# hack.net
KiCad netlist of a schematic drawn in EAGLE
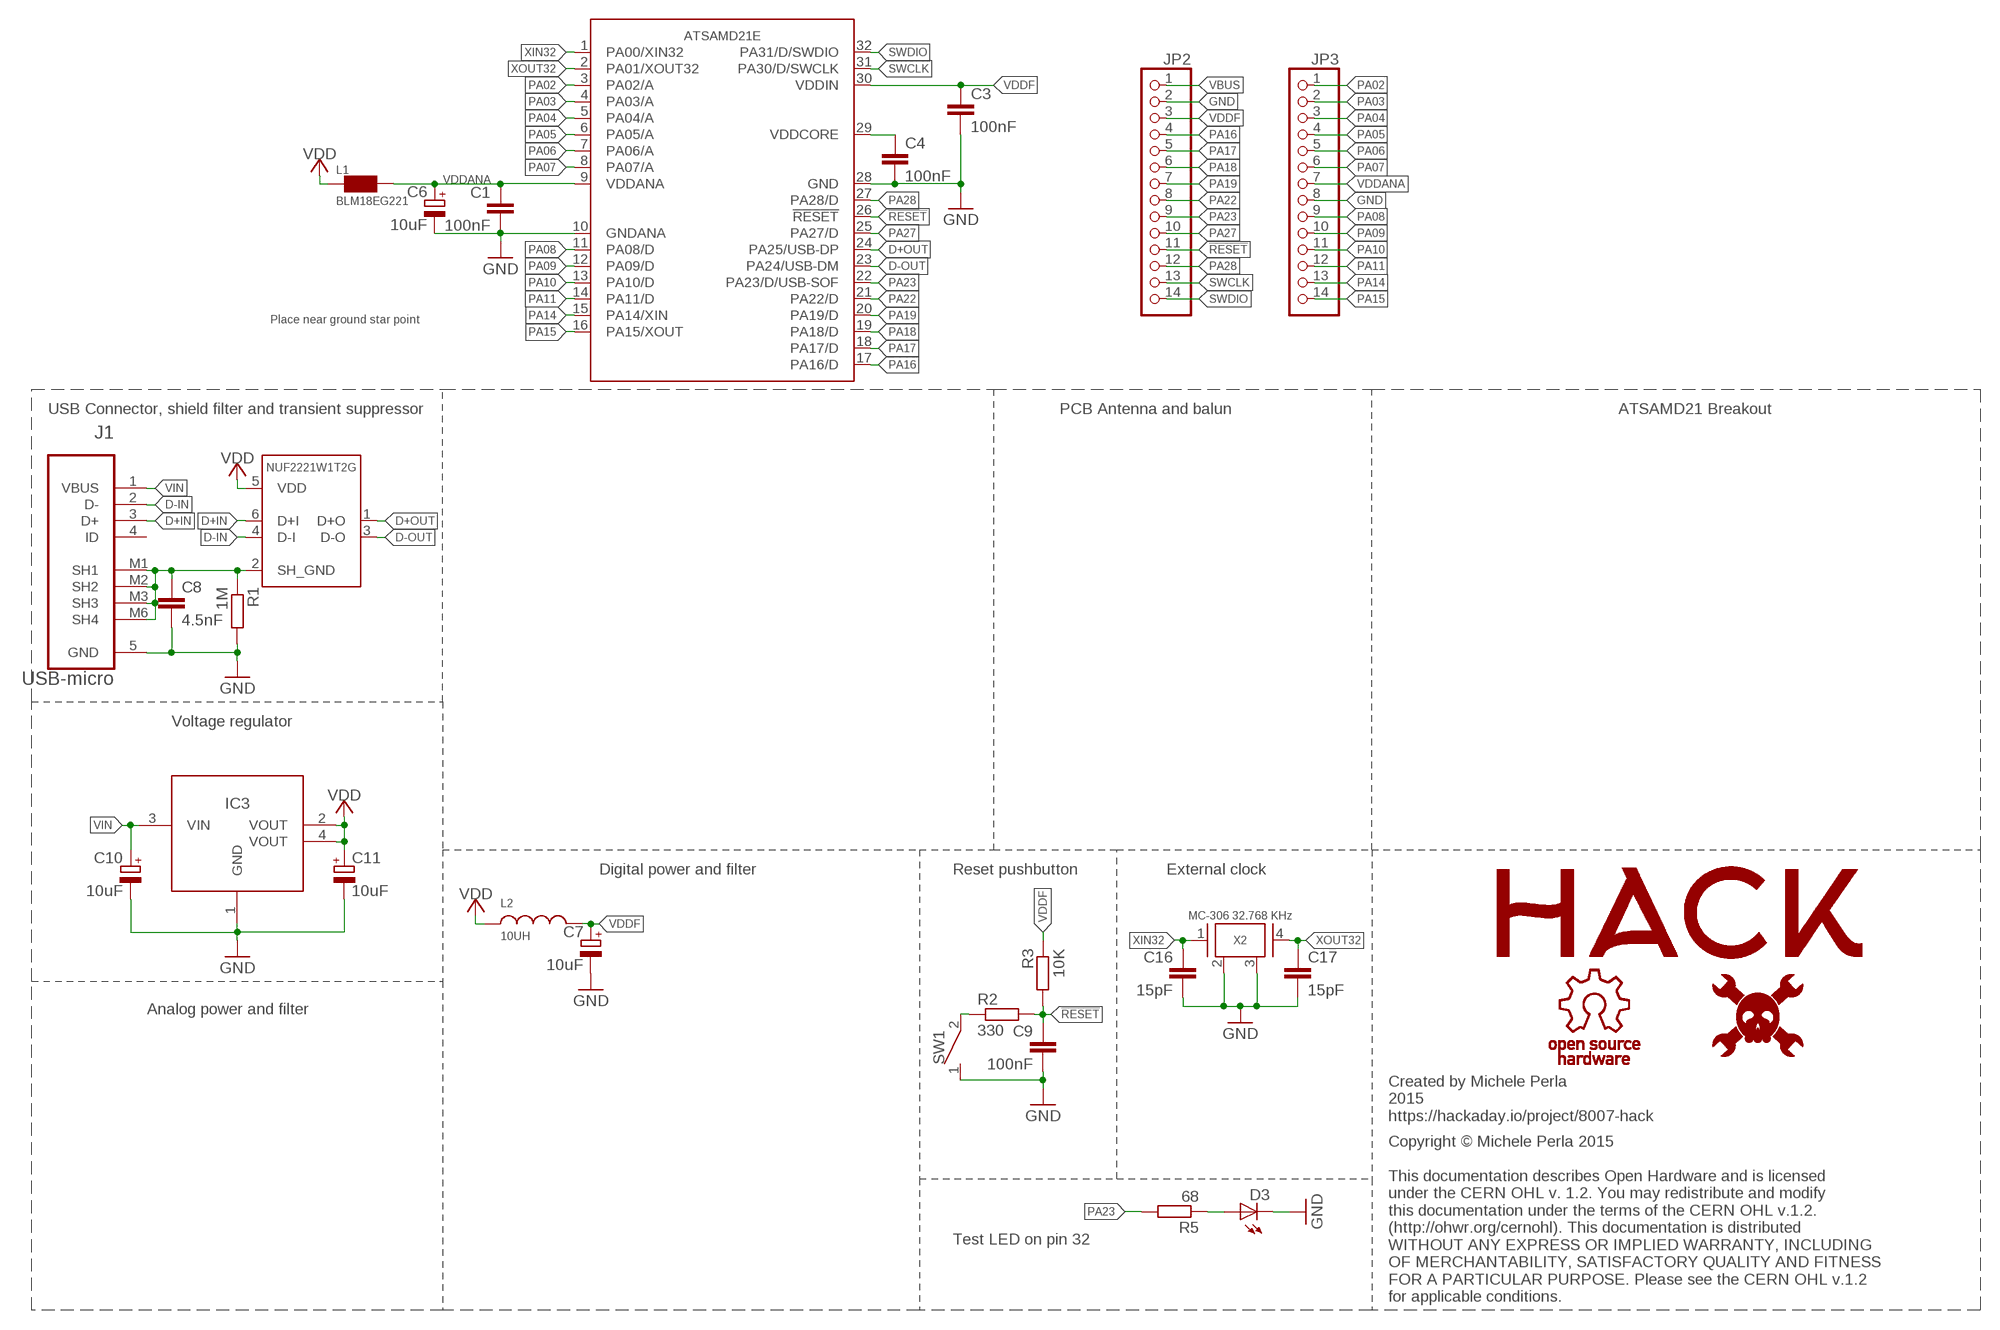
[diagram p0: schematic, sheet 1]

(export (version "E")
  (design (tool "Eeschema 10.0.6"))
  (components
    (comp (ref "C1")
      (value "100nF")
      (footprint "eagle-import:C0402")
      (libsource (lib "eagle-import") (part "C-EU"))
    )
    (comp (ref "C3")
      (value "100nF")
      (footprint "eagle-import:C0402")
      (libsource (lib "eagle-import") (part "C-EU"))
    )
    (comp (ref "C4")
      (value "100nF")
      (footprint "eagle-import:C0402")
      (libsource (lib "eagle-import") (part "C-EU"))
    )
    (comp (ref "C6")
      (value "10uF")
      (footprint "eagle-import:CT3216")
      (libsource (lib "eagle-import") (part "CPOL-EUCT3216"))
    )
    (comp (ref "C7")
      (value "10uF")
      (footprint "eagle-import:CT3216")
      (libsource (lib "eagle-import") (part "CPOL-EUCT3216"))
    )
    (comp (ref "C8")
      (value "4.5nF")
      (footprint "eagle-import:C0402")
      (libsource (lib "eagle-import") (part "C-EU"))
    )
    (comp (ref "C9")
      (value "100nF")
      (footprint "eagle-import:C0402")
      (libsource (lib "eagle-import") (part "C-EU"))
    )
    (comp (ref "C10")
      (value "10uF")
      (footprint "eagle-import:CT3216")
      (libsource (lib "eagle-import") (part "CPOL-EUCT3216"))
    )
    (comp (ref "C11")
      (value "10uF")
      (footprint "eagle-import:CT3216")
      (libsource (lib "eagle-import") (part "CPOL-EUCT3216"))
    )
    (comp (ref "C16")
      (value "15pF")
      (footprint "eagle-import:C0402")
      (libsource (lib "eagle-import") (part "C-EU"))
    )
    (comp (ref "C17")
      (value "15pF")
      (footprint "eagle-import:C0402")
      (libsource (lib "eagle-import") (part "C-EU"))
    )
    (comp (ref "D3")
      (value "LED")
      (footprint "eagle-import:LED-0603")
      (libsource (lib "eagle-import") (part "LED"))
    )
    (comp (ref "IC1")
      (value "NUF2221W1T2G")
      (footprint "eagle-import:SOT-363")
      (libsource (lib "eagle-import") (part "NUF2221W1T2G"))
    )
    (comp (ref "IC3")
      (value "LDO")
      (footprint "eagle-import:SOT-223-3")
      (libsource (lib "eagle-import") (part "LDO"))
    )
    (comp (ref "J1")
      (value "USB-micro")
      (footprint "eagle-import:MOLEX_47346-0001")
      (fields (field (name "MPN") "47346-0001"))
      (libsource (lib "eagle-import") (part "47346-0001"))
    )
    (comp (ref "JP2")
      (value "PINHD-1X14")
      (footprint "eagle-import:1X14")
      (libsource (lib "eagle-import") (part "PINHD-1X14"))
    )
    (comp (ref "JP3")
      (value "PINHD-1X14")
      (footprint "eagle-import:1X14")
      (libsource (lib "eagle-import") (part "PINHD-1X14"))
    )
    (comp (ref "L1")
      (value "BLM18EG221")
      (footprint "eagle-import:0603")
      (libsource (lib "eagle-import") (part "L"))
    )
    (comp (ref "L2")
      (value "10UH")
      (footprint "eagle-import:IND_ELLVXG")
      (fields (field (name "MPN") "ELLVFG100MC"))
      (libsource (lib "eagle-import") (part "ELL-VXGVFG100MC"))
    )
    (comp (ref "LOGO1")
      (value "HACK-LOGO")
      (footprint "eagle-import:HACK-LOGO")
      (libsource (lib "eagle-import") (part "HACK-LOGO"))
    )
    (comp (ref "R1")
      (value "1M")
      (footprint "eagle-import:R0603")
      (libsource (lib "eagle-import") (part "R-EU"))
    )
    (comp (ref "R2")
      (value "330")
      (footprint "eagle-import:R0603")
      (libsource (lib "eagle-import") (part "R-EU"))
    )
    (comp (ref "R3")
      (value "10K")
      (footprint "eagle-import:R0603")
      (libsource (lib "eagle-import") (part "R-EU"))
    )
    (comp (ref "R5")
      (value "68")
      (footprint "eagle-import:R0603")
      (libsource (lib "eagle-import") (part "R-EU"))
    )
    (comp (ref "SW1")
      (value "SPST3.5X6MM")
      (footprint "eagle-import:SWITCH-SMD-3.5X6MM")
      (libsource (lib "eagle-import") (part "SPST3.5X6MM"))
    )
    (comp (ref "U$5")
      (value "HAD-LOGO")
      (footprint "eagle-import:HAD-LOGO")
      (libsource (lib "eagle-import") (part "HAD-LOGO"))
    )
    (comp (ref "U$6")
      (value "OSHW-LOGO")
      (footprint "eagle-import:OSHW-LOGO")
      (libsource (lib "eagle-import") (part "OSHW-LOGO"))
    )
    (comp (ref "U1")
      (value "ATSAMD21E")
      (footprint "eagle-import:TQFP32")
      (libsource (lib "eagle-import") (part "ATSAMD21E"))
    )
    (comp (ref "X2")
      (value "MC-306 32.768 KHz")
      (footprint "eagle-import:MC-306")
      (libsource (lib "eagle-import") (part "XTALMC-306"))
    )
  )
  (nets
    (net (code "1") (name "/~{RESET}") (class "Default")
      (node (ref "C9") (pin "1") (pinfunction "1_1") (pintype "passive"))
      (node (ref "JP2") (pin "11") (pinfunction "11_11") (pintype "passive"))
      (node (ref "R2") (pin "2") (pinfunction "2_2") (pintype "passive"))
      (node (ref "R3") (pin "2") (pinfunction "2_2") (pintype "passive"))
      (node (ref "U1") (pin "26") (pinfunction "~{RESET}_26") (pintype "bidirectional"))
    )
    (net (code "2") (name "D+IN") (class "Default")
      (node (ref "IC1") (pin "6") (pinfunction "D+I_6") (pintype "bidirectional"))
      (node (ref "J1") (pin "3") (pinfunction "D+_3") (pintype "bidirectional"))
    )
    (net (code "3") (name "D+OUT") (class "Default")
      (node (ref "IC1") (pin "1") (pinfunction "D+O_1") (pintype "bidirectional"))
      (node (ref "U1") (pin "24") (pinfunction "PA25/USB-DP_24") (pintype "bidirectional"))
    )
    (net (code "4") (name "D-IN") (class "Default")
      (node (ref "IC1") (pin "4") (pinfunction "D-I_4") (pintype "bidirectional"))
      (node (ref "J1") (pin "2") (pinfunction "D-_2") (pintype "bidirectional"))
    )
    (net (code "5") (name "D-OUT") (class "Default")
      (node (ref "IC1") (pin "3") (pinfunction "D-O_3") (pintype "bidirectional"))
      (node (ref "U1") (pin "23") (pinfunction "PA24/USB-DM_23") (pintype "bidirectional"))
    )
    (net (code "6") (name "GND") (class "Default")
      (node (ref "C1") (pin "2") (pinfunction "2_2") (pintype "passive"))
      (node (ref "C10") (pin "-") (pinfunction "-_-") (pintype "passive"))
      (node (ref "C11") (pin "-") (pinfunction "-_-") (pintype "passive"))
      (node (ref "C16") (pin "2") (pinfunction "2_2") (pintype "passive"))
      (node (ref "C17") (pin "2") (pinfunction "2_2") (pintype "passive"))
      (node (ref "C3") (pin "2") (pinfunction "2_2") (pintype "passive"))
      (node (ref "C4") (pin "2") (pinfunction "2_2") (pintype "passive"))
      (node (ref "C6") (pin "-") (pinfunction "-_-") (pintype "passive"))
      (node (ref "C7") (pin "-") (pinfunction "-_-") (pintype "passive"))
      (node (ref "C8") (pin "2") (pinfunction "2_2") (pintype "passive"))
      (node (ref "C9") (pin "2") (pinfunction "2_2") (pintype "passive"))
      (node (ref "D3") (pin "C") (pinfunction "C_C") (pintype "passive"))
      (node (ref "IC3") (pin "1") (pinfunction "GND_1") (pintype "power_in"))
      (node (ref "J1") (pin "5") (pinfunction "GND_5") (pintype "power_in"))
      (node (ref "JP2") (pin "2") (pinfunction "2_2") (pintype "passive"))
      (node (ref "JP3") (pin "8") (pinfunction "8_8") (pintype "passive"))
      (node (ref "R1") (pin "2") (pinfunction "2_2") (pintype "passive"))
      (node (ref "SW1") (pin "1") (pinfunction "P$1_1") (pintype "bidirectional"))
      (node (ref "U1") (pin "10") (pinfunction "GNDANA_10") (pintype "power_in"))
      (node (ref "U1") (pin "28") (pinfunction "GND_28") (pintype "bidirectional"))
      (node (ref "X2") (pin "2") (pinfunction "GND_2") (pintype "power_in"))
      (node (ref "X2") (pin "3") (pinfunction "GND_3") (pintype "power_in"))
    )
    (net (code "7") (name "Net-(D3-PadA)") (class "Default")
      (node (ref "D3") (pin "A") (pinfunction "A_A") (pintype "passive"))
      (node (ref "R5") (pin "1") (pinfunction "1_1") (pintype "passive"))
    )
    (net (code "8") (name "Net-(IC1-SH_GND)") (class "Default")
      (node (ref "C8") (pin "1") (pinfunction "1_1") (pintype "passive"))
      (node (ref "IC1") (pin "2") (pinfunction "SH_GND_2") (pintype "power_in"))
      (node (ref "J1") (pin "M1") (pinfunction "SH1_M1") (pintype "bidirectional"))
      (node (ref "J1") (pin "M2") (pinfunction "SH2_M2") (pintype "bidirectional"))
      (node (ref "J1") (pin "M3") (pinfunction "SH3_M3") (pintype "bidirectional"))
      (node (ref "J1") (pin "M6") (pinfunction "SH4_M6") (pintype "bidirectional"))
      (node (ref "R1") (pin "1") (pinfunction "1_1") (pintype "passive"))
    )
    (net (code "9") (name "Net-(SW1-P$2)") (class "Default")
      (node (ref "R2") (pin "1") (pinfunction "1_1") (pintype "passive"))
      (node (ref "SW1") (pin "2") (pinfunction "P$2_2") (pintype "bidirectional"))
    )
    (net (code "10") (name "Net-(U1-VDDCORE)") (class "Default")
      (node (ref "C4") (pin "1") (pinfunction "1_1") (pintype "passive"))
      (node (ref "U1") (pin "29") (pinfunction "VDDCORE_29") (pintype "bidirectional"))
    )
    (net (code "11") (name "PA02") (class "Default")
      (node (ref "JP3") (pin "1") (pinfunction "1_1") (pintype "passive"))
      (node (ref "U1") (pin "3") (pinfunction "PA02/A_3") (pintype "bidirectional"))
    )
    (net (code "12") (name "PA03") (class "Default")
      (node (ref "JP3") (pin "2") (pinfunction "2_2") (pintype "passive"))
      (node (ref "U1") (pin "4") (pinfunction "PA03/A_4") (pintype "bidirectional"))
    )
    (net (code "13") (name "PA04") (class "Default")
      (node (ref "JP3") (pin "3") (pinfunction "3_3") (pintype "passive"))
      (node (ref "U1") (pin "5") (pinfunction "PA04/A_5") (pintype "bidirectional"))
    )
    (net (code "14") (name "PA05") (class "Default")
      (node (ref "JP3") (pin "4") (pinfunction "4_4") (pintype "passive"))
      (node (ref "U1") (pin "6") (pinfunction "PA05/A_6") (pintype "bidirectional"))
    )
    (net (code "15") (name "PA06") (class "Default")
      (node (ref "JP3") (pin "5") (pinfunction "5_5") (pintype "passive"))
      (node (ref "U1") (pin "7") (pinfunction "PA06/A_7") (pintype "bidirectional"))
    )
    (net (code "16") (name "PA07") (class "Default")
      (node (ref "JP3") (pin "6") (pinfunction "6_6") (pintype "passive"))
      (node (ref "U1") (pin "8") (pinfunction "PA07/A_8") (pintype "bidirectional"))
    )
    (net (code "17") (name "PA08") (class "Default")
      (node (ref "JP3") (pin "9") (pinfunction "9_9") (pintype "passive"))
      (node (ref "U1") (pin "11") (pinfunction "PA08/D_11") (pintype "bidirectional"))
    )
    (net (code "18") (name "PA09") (class "Default")
      (node (ref "JP3") (pin "10") (pinfunction "10_10") (pintype "passive"))
      (node (ref "U1") (pin "12") (pinfunction "PA09/D_12") (pintype "bidirectional"))
    )
    (net (code "19") (name "PA10") (class "Default")
      (node (ref "JP3") (pin "11") (pinfunction "11_11") (pintype "passive"))
      (node (ref "U1") (pin "13") (pinfunction "PA10/D_13") (pintype "bidirectional"))
    )
    (net (code "20") (name "PA11") (class "Default")
      (node (ref "JP3") (pin "12") (pinfunction "12_12") (pintype "passive"))
      (node (ref "U1") (pin "14") (pinfunction "PA11/D_14") (pintype "bidirectional"))
    )
    (net (code "21") (name "PA14") (class "Default")
      (node (ref "JP3") (pin "13") (pinfunction "13_13") (pintype "passive"))
      (node (ref "U1") (pin "15") (pinfunction "PA14/XIN_15") (pintype "bidirectional"))
    )
    (net (code "22") (name "PA15") (class "Default")
      (node (ref "JP3") (pin "14") (pinfunction "14_14") (pintype "passive"))
      (node (ref "U1") (pin "16") (pinfunction "PA15/XOUT_16") (pintype "bidirectional"))
    )
    (net (code "23") (name "PA16") (class "Default")
      (node (ref "JP2") (pin "4") (pinfunction "4_4") (pintype "passive"))
      (node (ref "U1") (pin "17") (pinfunction "PA16/D_17") (pintype "bidirectional"))
    )
    (net (code "24") (name "PA17") (class "Default")
      (node (ref "JP2") (pin "5") (pinfunction "5_5") (pintype "passive"))
      (node (ref "U1") (pin "18") (pinfunction "PA17/D_18") (pintype "bidirectional"))
    )
    (net (code "25") (name "PA18") (class "Default")
      (node (ref "JP2") (pin "6") (pinfunction "6_6") (pintype "passive"))
      (node (ref "U1") (pin "19") (pinfunction "PA18/D_19") (pintype "bidirectional"))
    )
    (net (code "26") (name "PA19") (class "Default")
      (node (ref "JP2") (pin "7") (pinfunction "7_7") (pintype "passive"))
      (node (ref "U1") (pin "20") (pinfunction "PA19/D_20") (pintype "bidirectional"))
    )
    (net (code "27") (name "PA22") (class "Default")
      (node (ref "JP2") (pin "8") (pinfunction "8_8") (pintype "passive"))
      (node (ref "U1") (pin "21") (pinfunction "PA22/D_21") (pintype "bidirectional"))
    )
    (net (code "28") (name "PA23") (class "Default")
      (node (ref "JP2") (pin "9") (pinfunction "9_9") (pintype "passive"))
      (node (ref "R5") (pin "2") (pinfunction "2_2") (pintype "passive"))
      (node (ref "U1") (pin "22") (pinfunction "PA23/D/USB-SOF_22") (pintype "bidirectional"))
    )
    (net (code "29") (name "PA27") (class "Default")
      (node (ref "JP2") (pin "10") (pinfunction "10_10") (pintype "passive"))
      (node (ref "U1") (pin "25") (pinfunction "PA27/D_25") (pintype "bidirectional"))
    )
    (net (code "30") (name "PA28") (class "Default")
      (node (ref "JP2") (pin "12") (pinfunction "12_12") (pintype "passive"))
      (node (ref "U1") (pin "27") (pinfunction "PA28/D_27") (pintype "bidirectional"))
    )
    (net (code "31") (name "SWCLK") (class "Default")
      (node (ref "JP2") (pin "13") (pinfunction "13_13") (pintype "passive"))
      (node (ref "U1") (pin "31") (pinfunction "PA30/D/SWCLK_31") (pintype "bidirectional"))
    )
    (net (code "32") (name "SWDIO") (class "Default")
      (node (ref "JP2") (pin "14") (pinfunction "14_14") (pintype "passive"))
      (node (ref "U1") (pin "32") (pinfunction "PA31/D/SWDIO_32") (pintype "bidirectional"))
    )
    (net (code "33") (name "VBUS") (class "Default")
      (node (ref "JP2") (pin "1") (pinfunction "1_1") (pintype "passive"))
    )
    (net (code "34") (name "VDD") (class "Default")
      (node (ref "C11") (pin "+") (pinfunction "+_+") (pintype "passive"))
      (node (ref "IC1") (pin "5") (pinfunction "VDD_5") (pintype "power_in"))
      (node (ref "IC3") (pin "2") (pinfunction "VOUT_2") (pintype "power_in"))
      (node (ref "IC3") (pin "4") (pinfunction "VOUT_4") (pintype "power_in"))
      (node (ref "L1") (pin "1") (pinfunction "1_1") (pintype "passive"))
      (node (ref "L2") (pin "2") (pinfunction "2_2") (pintype "passive"))
    )
    (net (code "35") (name "VDDANA") (class "Default")
      (node (ref "C1") (pin "1") (pinfunction "1_1") (pintype "passive"))
      (node (ref "C6") (pin "+") (pinfunction "+_+") (pintype "passive"))
      (node (ref "JP3") (pin "7") (pinfunction "7_7") (pintype "passive"))
      (node (ref "L1") (pin "2") (pinfunction "2_2") (pintype "passive"))
      (node (ref "U1") (pin "9") (pinfunction "VDDANA_9") (pintype "power_in"))
    )
    (net (code "36") (name "VDDF") (class "Default")
      (node (ref "C3") (pin "1") (pinfunction "1_1") (pintype "passive"))
      (node (ref "C7") (pin "+") (pinfunction "+_+") (pintype "passive"))
      (node (ref "JP2") (pin "3") (pinfunction "3_3") (pintype "passive"))
      (node (ref "L2") (pin "1") (pinfunction "1_1") (pintype "passive"))
      (node (ref "R3") (pin "1") (pinfunction "1_1") (pintype "passive"))
      (node (ref "U1") (pin "30") (pinfunction "VDDIN_30") (pintype "bidirectional"))
    )
    (net (code "37") (name "VIN") (class "Default")
      (node (ref "C10") (pin "+") (pinfunction "+_+") (pintype "passive"))
      (node (ref "IC3") (pin "3") (pinfunction "VIN_3") (pintype "input"))
      (node (ref "J1") (pin "1") (pinfunction "VBUS_1") (pintype "power_in"))
    )
    (net (code "38") (name "XIN32") (class "Default")
      (node (ref "C16") (pin "1") (pinfunction "1_1") (pintype "passive"))
      (node (ref "U1") (pin "1") (pinfunction "PA00/XIN32_1") (pintype "bidirectional"))
      (node (ref "X2") (pin "1") (pinfunction "P$1_1") (pintype "bidirectional"))
    )
    (net (code "39") (name "XOUT32") (class "Default")
      (node (ref "C17") (pin "1") (pinfunction "1_1") (pintype "passive"))
      (node (ref "U1") (pin "2") (pinfunction "PA01/XOUT32_2") (pintype "bidirectional"))
      (node (ref "X2") (pin "4") (pinfunction "P$3_4") (pintype "bidirectional"))
    )
    (net (code "40") (name "unconnected-(J1-ID-Pad4)") (class "Default")
      (node (ref "J1") (pin "4") (pinfunction "ID_4") (pintype "bidirectional"))
    )
  )
)
